# Pocket-Boost-Converter.net
KiCad netlist of a schematic drawn in EAGLE
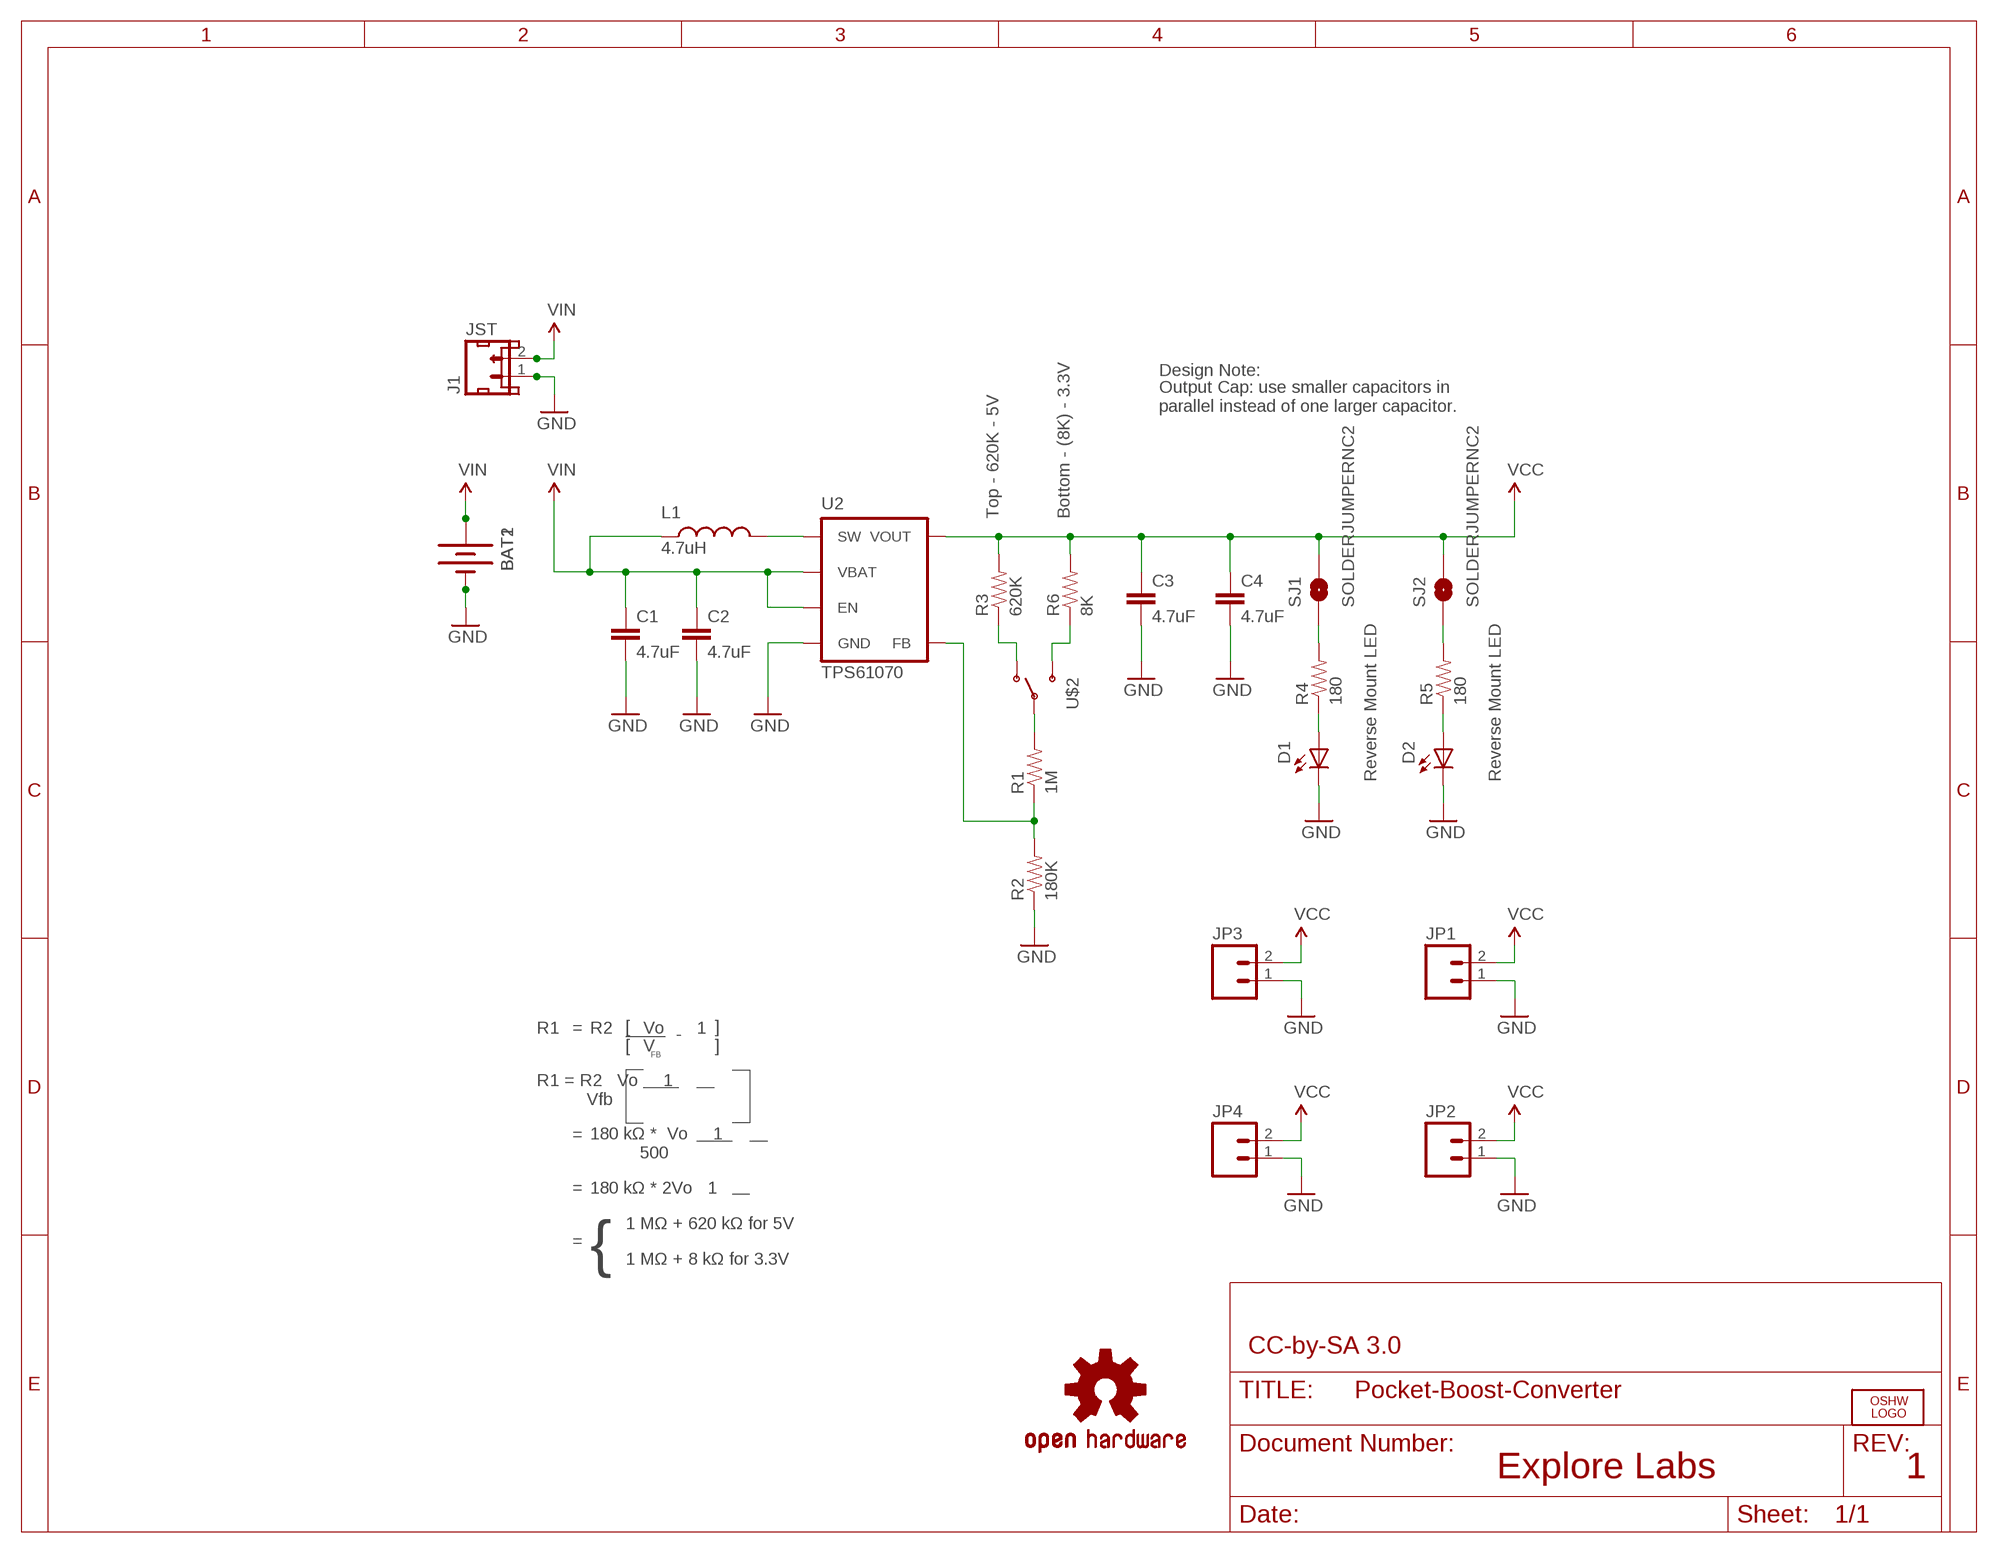
[diagram p0: schematic, sheet 1]

(export (version "E")
  (design (tool "Eeschema 10.0.6"))
  (components
    (comp (ref "BAT1")
      (value "BATTERYONE-HOLE-REMOVED-FOR-REV-MNT-LED")
      (footprint "eagle-import:BATTERY-AA-HOLDER-BBPS")
      (libsource (lib "eagle-import") (part "BATTERYONE-HOLE-REMOVED-FOR-REV-MNT-LED"))
    )
    (comp (ref "BAT2")
      (value "BATTERYNO-HOLES")
      (footprint "eagle-import:BATTERY-2AA-HOLDER-BBPS")
      (libsource (lib "eagle-import") (part "BATTERYNO-HOLES"))
    )
    (comp (ref "C1")
      (value "4.7uF")
      (footprint "eagle-import:0603-CAP")
      (libsource (lib "eagle-import") (part "CAP0603-CAP"))
    )
    (comp (ref "C2")
      (value "4.7uF")
      (footprint "eagle-import:0603-CAP")
      (libsource (lib "eagle-import") (part "CAP0603-CAP"))
    )
    (comp (ref "C3")
      (value "4.7uF")
      (footprint "eagle-import:0603-CAP")
      (libsource (lib "eagle-import") (part "CAP0603-CAP"))
    )
    (comp (ref "C4")
      (value "4.7uF")
      (footprint "eagle-import:0603-CAP")
      (libsource (lib "eagle-import") (part "CAP0603-CAP"))
    )
    (comp (ref "D1")
      (value "Reverse Mount LED")
      (footprint "eagle-import:LED-REV-MOUNT")
      (libsource (lib "eagle-import") (part "LED-GREEN"))
    )
    (comp (ref "D2")
      (value "Reverse Mount LED")
      (footprint "eagle-import:LED-REV-MOUNT")
      (libsource (lib "eagle-import") (part "LED-GREEN"))
    )
    (comp (ref "J1")
      (value "JST_2MM_MALE")
      (footprint "eagle-import:JST-2-SMD")
      (libsource (lib "eagle-import") (part "JST_2MM_MALE"))
    )
    (comp (ref "JP1")
      (value "M02PTH")
      (footprint "eagle-import:1X02")
      (libsource (lib "eagle-import") (part "M02PTH"))
    )
    (comp (ref "JP2")
      (value "M02PTH")
      (footprint "eagle-import:1X02")
      (libsource (lib "eagle-import") (part "M02PTH"))
    )
    (comp (ref "JP3")
      (value "M02PTH")
      (footprint "eagle-import:1X02")
      (libsource (lib "eagle-import") (part "M02PTH"))
    )
    (comp (ref "JP4")
      (value "M02PTH")
      (footprint "eagle-import:1X02")
      (libsource (lib "eagle-import") (part "M02PTH"))
    )
    (comp (ref "JST")
      (value "M02-JST-2-PTH-NO_SILK")
      (footprint "eagle-import:JST-2-PTH-NS")
      (libsource (lib "eagle-import") (part "M02-JST-2-PTH-NO_SILK"))
    )
    (comp (ref "L1")
      (value "4.7uH")
      (footprint "eagle-import:INDUCTOR-MSS4020")
      (libsource (lib "eagle-import") (part "INDUCTOR"))
    )
    (comp (ref "LOGO1")
      (value "OSHW_LOGO_FILLX0200-NT")
      (footprint "eagle-import:OSHW_FILLX200_NOTEXT")
      (libsource (lib "eagle-import") (part "OSHW_LOGO_FILLX0200-NT"))
    )
    (comp (ref "LOGO2")
      (value "OSHW-LOGOS")
      (footprint "eagle-import:OSHW-LOGO-S")
      (libsource (lib "eagle-import") (part "OSHW-LOGOS"))
    )
    (comp (ref "R1")
      (value "1M")
      (footprint "eagle-import:0603-RES")
      (libsource (lib "eagle-import") (part "RESISTOR0603-RES"))
    )
    (comp (ref "R2")
      (value "180K")
      (footprint "eagle-import:0603-RES")
      (libsource (lib "eagle-import") (part "RESISTOR0603-RES"))
    )
    (comp (ref "R3")
      (value "620K")
      (footprint "eagle-import:0603-RES")
      (libsource (lib "eagle-import") (part "RESISTOR0603-RES"))
    )
    (comp (ref "R4")
      (value "180")
      (footprint "eagle-import:0603-RES")
      (libsource (lib "eagle-import") (part "RESISTOR0603-RES"))
    )
    (comp (ref "R5")
      (value "180")
      (footprint "eagle-import:0603-RES")
      (libsource (lib "eagle-import") (part "RESISTOR0603-RES"))
    )
    (comp (ref "R6")
      (value "8K")
      (footprint "eagle-import:0603-RES")
      (libsource (lib "eagle-import") (part "RESISTOR0603-RES"))
    )
    (comp (ref "SJ1")
      (value "SOLDERJUMPERNC2")
      (footprint "eagle-import:SJ_2S-NOTRACE")
      (libsource (lib "eagle-import") (part "SOLDERJUMPERNC2"))
    )
    (comp (ref "SJ2")
      (value "SOLDERJUMPERNC2")
      (footprint "eagle-import:SJ_2S-NOTRACE")
      (libsource (lib "eagle-import") (part "SOLDERJUMPERNC2"))
    )
    (comp (ref "U$2")
      (value "SWITCH_SPDTSMD-NO-HOLES")
      (footprint "eagle-import:SWITCH-SPST-SMD-A-FOR-BBPS")
      (libsource (lib "eagle-import") (part "SWITCH_SPDTSMD-NO-HOLES"))
    )
    (comp (ref "U2")
      (value "TPS61070")
      (footprint "eagle-import:DDC")
      (libsource (lib "eagle-import") (part "TPS61070"))
    )
  )
  (nets
    (net (code "1") (name "GND") (class "Default")
      (node (ref "BAT1") (pin "GND") (pinfunction "-_GND") (pintype "power_in"))
      (node (ref "BAT2") (pin "GND") (pinfunction "-_GND") (pintype "power_in"))
      (node (ref "C1") (pin "2") (pinfunction "2_2") (pintype "passive"))
      (node (ref "C2") (pin "2") (pinfunction "2_2") (pintype "passive"))
      (node (ref "C3") (pin "2") (pinfunction "2_2") (pintype "passive"))
      (node (ref "C4") (pin "2") (pinfunction "2_2") (pintype "passive"))
      (node (ref "D1") (pin "CATHODE") (pinfunction "CATHODE_CATHODE") (pintype "passive"))
      (node (ref "D2") (pin "CATHODE") (pinfunction "CATHODE_CATHODE") (pintype "passive"))
      (node (ref "J1") (pin "1") (pinfunction "-_1") (pintype "bidirectional"))
      (node (ref "JP1") (pin "1") (pinfunction "1_1") (pintype "passive"))
      (node (ref "JP2") (pin "1") (pinfunction "1_1") (pintype "passive"))
      (node (ref "JP3") (pin "1") (pinfunction "1_1") (pintype "passive"))
      (node (ref "JP4") (pin "1") (pinfunction "1_1") (pintype "passive"))
      (node (ref "JST") (pin "1") (pinfunction "1_1") (pintype "passive"))
      (node (ref "R2") (pin "1") (pinfunction "1_1") (pintype "passive"))
      (node (ref "U2") (pin "2") (pinfunction "GND_2") (pintype "power_in"))
    )
    (net (code "2") (name "Net-(D1-PadANODE)") (class "Default")
      (node (ref "D1") (pin "ANODE") (pinfunction "ANODE_ANODE") (pintype "passive"))
      (node (ref "R4") (pin "1") (pinfunction "1_1") (pintype "passive"))
    )
    (net (code "3") (name "Net-(D2-PadANODE)") (class "Default")
      (node (ref "D2") (pin "ANODE") (pinfunction "ANODE_ANODE") (pintype "passive"))
      (node (ref "R5") (pin "1") (pinfunction "1_1") (pintype "passive"))
    )
    (net (code "4") (name "Net-(R1-Pad2)") (class "Default")
      (node (ref "R1") (pin "2") (pinfunction "2_2") (pintype "passive"))
      (node (ref "U$2") (pin "B") (pinfunction "BC-IN_B") (pintype "passive"))
      (node (ref "U$2") (pin "C") (pinfunction "BC-IN_C") (pintype "passive"))
    )
    (net (code "5") (name "Net-(R4-Pad2)") (class "Default")
      (node (ref "R4") (pin "2") (pinfunction "2_2") (pintype "passive"))
      (node (ref "SJ1") (pin "1") (pinfunction "1_1") (pintype "passive"))
    )
    (net (code "6") (name "Net-(R5-Pad2)") (class "Default")
      (node (ref "R5") (pin "2") (pinfunction "2_2") (pintype "passive"))
      (node (ref "SJ2") (pin "1") (pinfunction "1_1") (pintype "passive"))
    )
    (net (code "7") (name "Net-(U$2-A-OUT)") (class "Default")
      (node (ref "R3") (pin "1") (pinfunction "1_1") (pintype "passive"))
      (node (ref "U$2") (pin "A") (pinfunction "A-OUT_A") (pintype "passive"))
    )
    (net (code "8") (name "Net-(U$2-D-OUT)") (class "Default")
      (node (ref "R6") (pin "1") (pinfunction "1_1") (pintype "passive"))
      (node (ref "U$2") (pin "D") (pinfunction "D-OUT_D") (pintype "passive"))
    )
    (net (code "9") (name "Net-(U2-FB)") (class "Default")
      (node (ref "R1") (pin "1") (pinfunction "1_1") (pintype "passive"))
      (node (ref "R2") (pin "2") (pinfunction "2_2") (pintype "passive"))
      (node (ref "U2") (pin "4") (pinfunction "FB_4") (pintype "input"))
    )
    (net (code "10") (name "Net-(U2-SW)") (class "Default")
      (node (ref "L1") (pin "2") (pinfunction "2_2") (pintype "passive"))
      (node (ref "U2") (pin "1") (pinfunction "SW_1") (pintype "passive"))
    )
    (net (code "11") (name "VCC") (class "Default")
      (node (ref "C3") (pin "1") (pinfunction "1_1") (pintype "passive"))
      (node (ref "C4") (pin "1") (pinfunction "1_1") (pintype "passive"))
      (node (ref "JP1") (pin "2") (pinfunction "2_2") (pintype "passive"))
      (node (ref "JP2") (pin "2") (pinfunction "2_2") (pintype "passive"))
      (node (ref "JP3") (pin "2") (pinfunction "2_2") (pintype "passive"))
      (node (ref "JP4") (pin "2") (pinfunction "2_2") (pintype "passive"))
      (node (ref "R3") (pin "2") (pinfunction "2_2") (pintype "passive"))
      (node (ref "R6") (pin "2") (pinfunction "2_2") (pintype "passive"))
      (node (ref "SJ1") (pin "2") (pinfunction "2_2") (pintype "passive"))
      (node (ref "SJ2") (pin "2") (pinfunction "2_2") (pintype "passive"))
      (node (ref "U2") (pin "5") (pinfunction "VOUT_5") (pintype "output"))
    )
    (net (code "12") (name "VIN") (class "Default")
      (node (ref "BAT1") (pin "PWR") (pinfunction "+_PWR") (pintype "power_in"))
      (node (ref "BAT2") (pin "PWR") (pinfunction "+_PWR") (pintype "power_in"))
      (node (ref "C1") (pin "1") (pinfunction "1_1") (pintype "passive"))
      (node (ref "C2") (pin "1") (pinfunction "1_1") (pintype "passive"))
      (node (ref "J1") (pin "2") (pinfunction "+_2") (pintype "bidirectional"))
      (node (ref "JST") (pin "2") (pinfunction "2_2") (pintype "passive"))
      (node (ref "L1") (pin "1") (pinfunction "1_1") (pintype "passive"))
      (node (ref "U2") (pin "3") (pinfunction "EN_3") (pintype "input"))
      (node (ref "U2") (pin "6") (pinfunction "VBAT_6") (pintype "input"))
    )
    (net (code "13") (name "unconnected-(J1-PAD1-PadNC1)") (class "Default")
      (node (ref "J1") (pin "NC1") (pinfunction "PAD1_NC1") (pintype "bidirectional"))
    )
    (net (code "14") (name "unconnected-(J1-PAD2-PadNC2)") (class "Default")
      (node (ref "J1") (pin "NC2") (pinfunction "PAD2_NC2") (pintype "bidirectional"))
    )
  )
)
